# MCU.net
KiCad netlist of a schematic drawn in Altium Designer
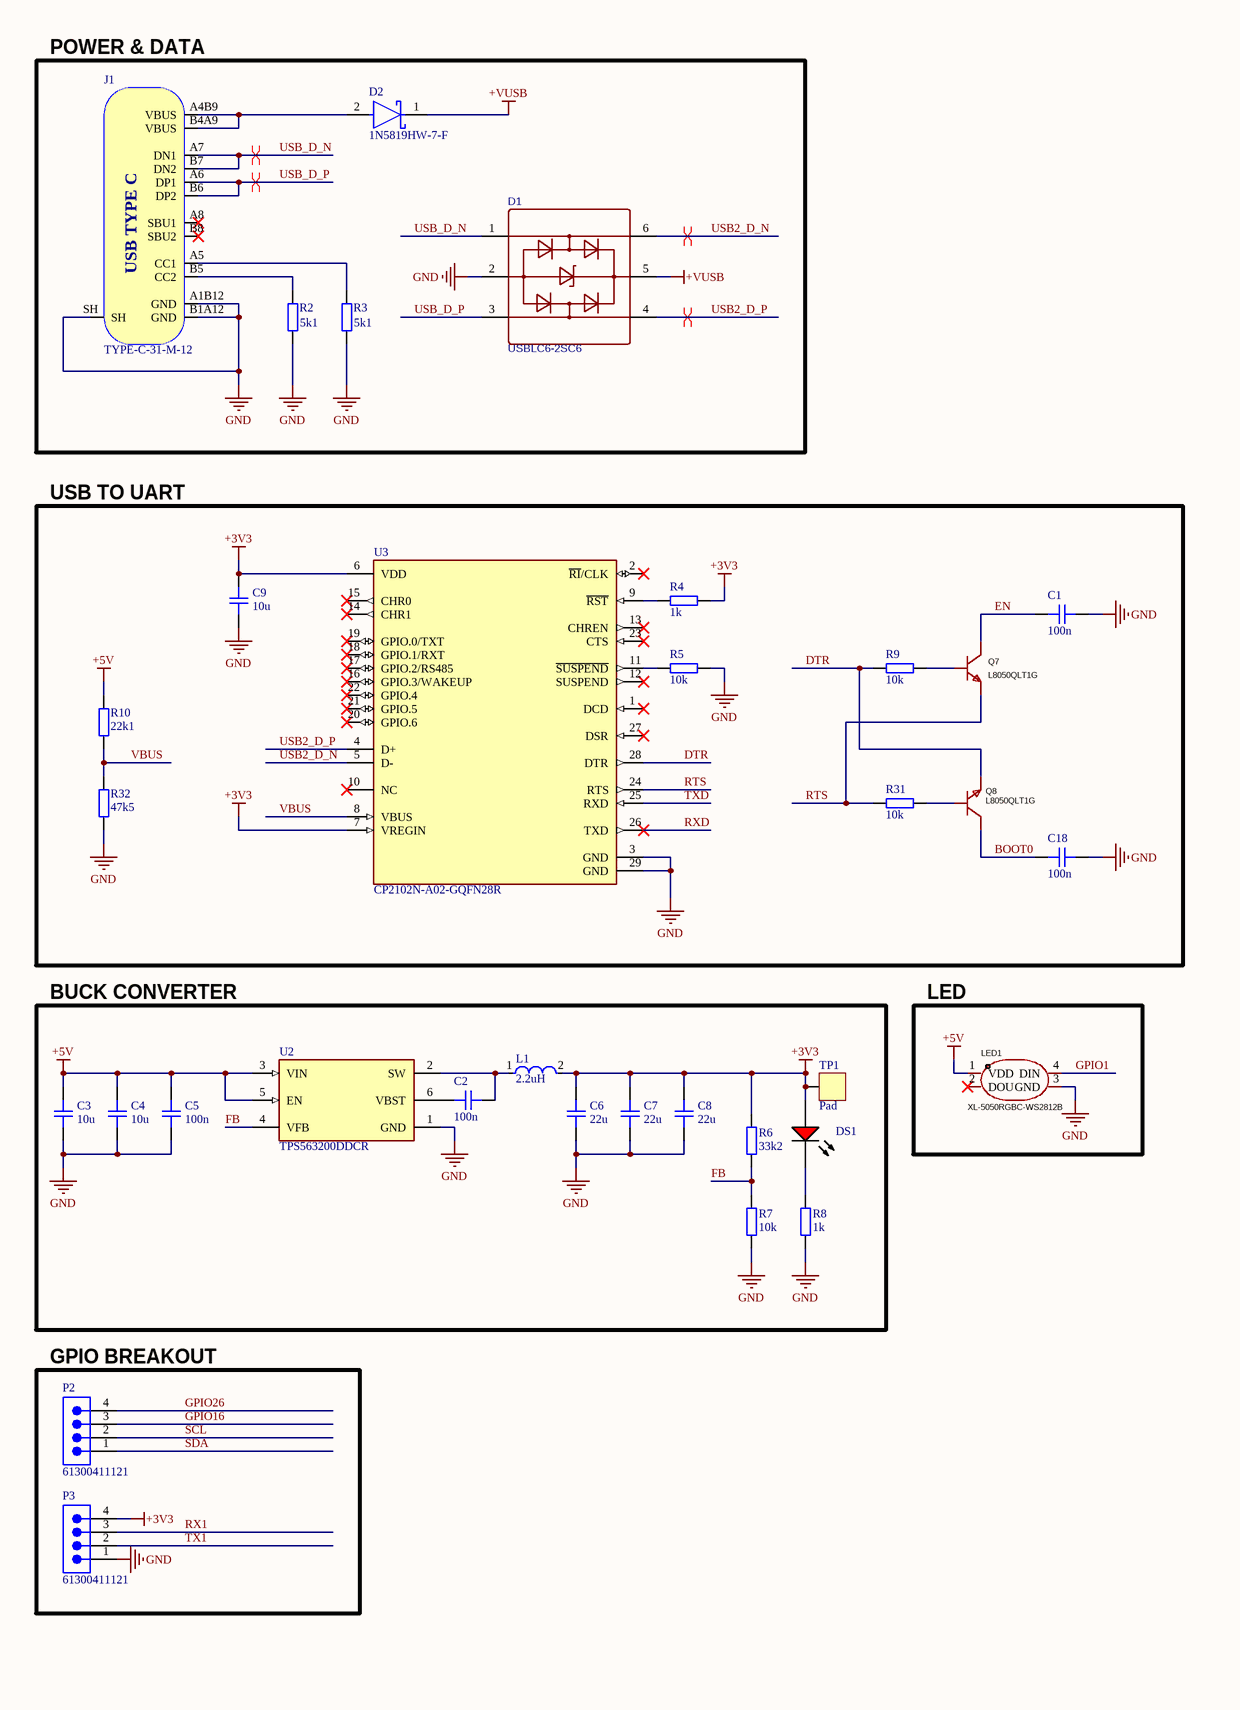
[diagram p0: MCU.SchDoc, left]
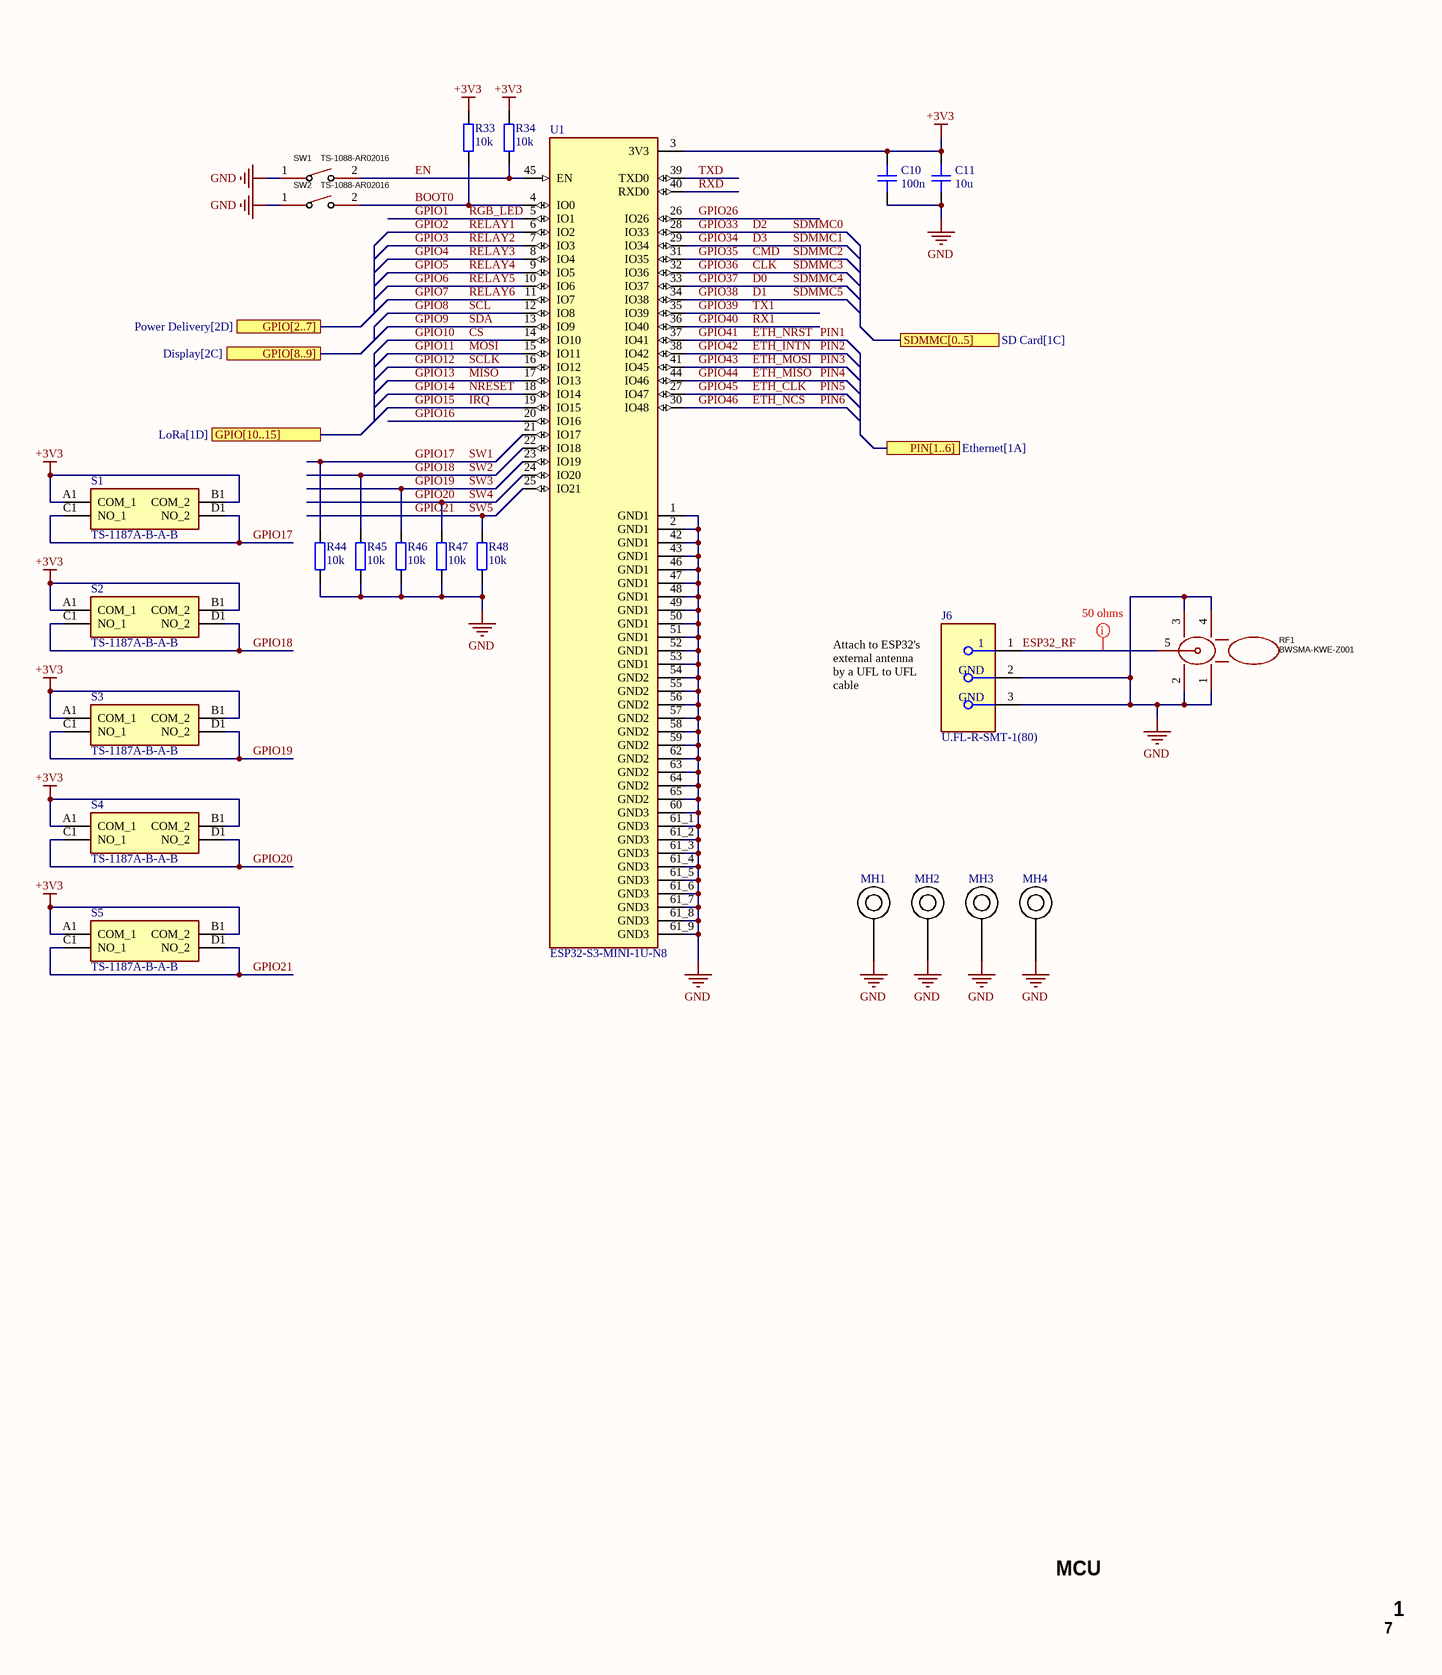
[diagram p1: MCU.SchDoc, right]

(export (version "E")
  (design (tool "Eeschema 10.0.6"))
  (components
    (comp (ref "C1")
      (value "CL05B104KB54PNC")
      (footprint "CAP_0402")
      (description "Capacitor SMD 0402")
      (fields (field (name "RATING") "100n"))
      (libsource (lib "Schematic-Lib-PhilsLab") (part "CAP_0402"))
    )
    (comp (ref "C2")
      (value "CL05B104KB54PNC")
      (footprint "CAP_0402")
      (description "Capacitor SMD 0402")
      (fields (field (name "RATING") "100n"))
      (libsource (lib "Schematic-Lib-PhilsLab") (part "CAP_0402"))
    )
    (comp (ref "C3")
      (value "10u")
      (footprint "CAP_0402")
      (description "Capacitor SMD 0402")
      (fields (field (name "Comment") "CL05A106MQ5NUNC"))
      (libsource (lib "Schematic-Lib-PhilsLab") (part "CAP_0402"))
    )
    (comp (ref "C4")
      (value "10u")
      (footprint "CAP_0402")
      (description "Capacitor SMD 0402")
      (fields (field (name "Comment") "CL05A106MQ5NUNC"))
      (libsource (lib "Schematic-Lib-PhilsLab") (part "CAP_0402"))
    )
    (comp (ref "C5")
      (value "CL05B104KB54PNC")
      (footprint "CAP_0402")
      (description "Capacitor SMD 0402")
      (fields (field (name "RATING") "100n"))
      (libsource (lib "Schematic-Lib-PhilsLab") (part "CAP_0402"))
    )
    (comp (ref "C6")
      (value "GRM158R61A226ME15D")
      (footprint "CAP_0402")
      (description "Capacitor SMD 0402")
      (fields (field (name "RATING") "22u"))
      (libsource (lib "Schematic-Lib-PhilsLab") (part "CAP_0402"))
    )
    (comp (ref "C7")
      (value "GRM158R61A226ME15D")
      (footprint "CAP_0402")
      (description "Capacitor SMD 0402")
      (fields (field (name "RATING") "22u"))
      (libsource (lib "Schematic-Lib-PhilsLab") (part "CAP_0402"))
    )
    (comp (ref "C8")
      (value "GRM158R61A226ME15D")
      (footprint "CAP_0402")
      (description "Capacitor SMD 0402")
      (fields (field (name "RATING") "22u"))
      (libsource (lib "Schematic-Lib-PhilsLab") (part "CAP_0402"))
    )
    (comp (ref "C9")
      (value "10u")
      (footprint "CAP_0402")
      (description "Capacitor SMD 0402")
      (fields (field (name "Comment") "CL05A106MQ5NUNC"))
      (libsource (lib "Schematic-Lib-PhilsLab") (part "CAP_0402"))
    )
    (comp (ref "C10")
      (value "CL05B104KB54PNC")
      (footprint "CAP_0402")
      (description "Capacitor SMD 0402")
      (fields (field (name "RATING") "100n"))
      (libsource (lib "Schematic-Lib-PhilsLab") (part "CAP_0402"))
    )
    (comp (ref "C11")
      (value "10u")
      (footprint "CAP_0402")
      (description "Capacitor SMD 0402")
      (fields (field (name "Comment") "CL05A106MQ5NUNC"))
      (libsource (lib "Schematic-Lib-PhilsLab") (part "CAP_0402"))
    )
    (comp (ref "C18")
      (value "CL05B104KB54PNC")
      (footprint "CAP_0402")
      (description "Capacitor SMD 0402")
      (fields (field (name "RATING") "100n"))
      (libsource (lib "Schematic-Lib-PhilsLab") (part "CAP_0402"))
    )
    (comp (ref "D1")
      (value "USBLC6-2SC6")
      (footprint "SOT-23-6_L2.9-W1.6-P0.95-LS2.8-BL")
      (fields (field (name "MANUFACTURER") "ST(意法半导体)"))
      (libsource (lib "JLCPCB_parts_library") (part "USBLC6-2SC6"))
    )
    (comp (ref "D2")
      (value "1N5819HW-7-F")
      (footprint "FP-SOD123-IPC_A")
      (description "DIODE SCHOTTKY 40V 1A SOD123")
      (libsource (lib "Altium Content Vault") (part "1d6ec82d83fb6aee721767c19dac4b9"))
    )
    (comp (ref "DS1")
      (value "LTST-C170KRKT")
      (footprint "LTST-C170KRKT_V")
      (description "LED Red, 75 mW, 54 mcd, -55 to 85 degC, 2-Pin SMD, RoHS, Tape and Reel")
      (fields (field (name "MANUFACTURER") "Lite-On"))
      (libsource (lib "Altium Content Vault") (part "LED-RED-AK-2"))
    )
    (comp (ref "J1")
      (value "TYPE-C-31-M-12")
      (footprint "TYPE-C-31-M-12")
      (description "USB Type C Connector Horizontal SMT")
      (fields (field (name "MANUFACTURER") "Koren Hroparts"))
      (libsource (lib "Schematic-Lib-PhilsLab") (part "TYPE-C-31-M-12"))
    )
    (comp (ref "J6")
      (value "U.FL-R-SMT-1(80)")
      (footprint "FP-U_FL-R-SMT-1_80-MFG")
      (description "CONN U.FL RCPT STR 50 OHM SMD")
      (libsource (lib "Altium Content Vault") (part "ad010367dc7cd7c7a13299a56582dd6"))
    )
    (comp (ref "L1")
      (value "IHLP1212BZER2R2M11")
      (footprint "FP-IHLP-1212BZ-11-MFG")
      (description "FIXED IND 2.2UH 3A 46 MOHM SMD")
      (fields (field (name "INDUCTANCE") "2.2uH") (field (name "TOLERANCE") "20%"))
      (libsource (lib "Altium Content Vault") (part "725321dda6339637d4d059423bc1c3c"))
    )
    (comp (ref "LED1")
      (value "XL-5050RGBC-WS2812B")
      (footprint "LED-SMD_4P-L5.0-W5.0-BL_XL-5050RGBC")
      (fields (field (name "MANUFACTURER") "XINGLIGHT(成兴光)"))
      (libsource (lib "JLCPCB_parts_library") (part "XL-5050RGBC-WS2812B_1"))
    )
    (comp (ref "MH1")
      (value "M3PlatedMountingHole2")
      (footprint "PCBComponent_1 - duplicate")
      (libsource (lib "JLCPCB_parts_library") (part "M3PlatedMountingHole2"))
    )
    (comp (ref "MH2")
      (value "M3PlatedMountingHole2")
      (footprint "PCBComponent_1 - duplicate")
      (libsource (lib "JLCPCB_parts_library") (part "M3PlatedMountingHole2"))
    )
    (comp (ref "MH3")
      (value "M3PlatedMountingHole2")
      (footprint "PCBComponent_1 - duplicate")
      (libsource (lib "JLCPCB_parts_library") (part "M3PlatedMountingHole2"))
    )
    (comp (ref "MH4")
      (value "M3PlatedMountingHole2")
      (footprint "PCBComponent_1 - duplicate")
      (libsource (lib "JLCPCB_parts_library") (part "M3PlatedMountingHole2"))
    )
    (comp (ref "P2")
      (value "61300411121")
      (footprint "61300411121")
      (libsource (lib "Altium Content Vault") (part "Header_Male_1R_04P"))
    )
    (comp (ref "P3")
      (value "61300411121")
      (footprint "61300411121")
      (libsource (lib "Altium Content Vault") (part "Header_Male_1R_04P"))
    )
    (comp (ref "Q7")
      (value "L8050QLT1G")
      (footprint "SOT-23-3_L2.9-W1.3-P1.90-LS2.4-BR")
      (fields (field (name "MANUFACTURER") "LRC(乐山无线电)"))
      (libsource (lib "JLCPCB_parts_library") (part "L8050QLT1G"))
    )
    (comp (ref "Q8")
      (value "L8050QLT1G")
      (footprint "SOT-23-3_L2.9-W1.3-P1.90-LS2.4-BR")
      (fields (field (name "MANUFACTURER") "LRC(乐山无线电)"))
      (libsource (lib "JLCPCB_parts_library") (part "L8050QLT1G"))
    )
    (comp (ref "R2")
      (value "5k1")
      (footprint "RES_0402")
      (description "Resistor SMD 0402 5.1k")
      (fields (field (name "Comment") "0402WGF5101TCE"))
      (libsource (lib "Schematic-Lib-PhilsLab") (part "RES_0402"))
    )
    (comp (ref "R3")
      (value "5k1")
      (footprint "RES_0402")
      (description "Resistor SMD 0402 5.1k")
      (fields (field (name "Comment") "0402WGF5101TCE"))
      (libsource (lib "Schematic-Lib-PhilsLab") (part "RES_0402"))
    )
    (comp (ref "R4")
      (value "1k")
      (footprint "RES_0402")
      (description "Resistor SMD 0402")
      (fields (field (name "Comment") "0402WGF1001TCE"))
      (libsource (lib "Schematic-Lib-PhilsLab") (part "RES_0402"))
    )
    (comp (ref "R5")
      (value "10k")
      (footprint "RES_0402")
      (description "Resistor SMD 0402")
      (fields (field (name "Comment") "0402WGF1002TCE"))
      (libsource (lib "Schematic-Lib-PhilsLab") (part "RES_0402"))
    )
    (comp (ref "R6")
      (value "33k2")
      (footprint "RES_0402")
      (description "Resistor SMD 0402")
      (fields (field (name "Comment") "0402WGF3322TCE"))
      (libsource (lib "Schematic-Lib-PhilsLab") (part "RES_0402"))
    )
    (comp (ref "R7")
      (value "10k")
      (footprint "RES_0402")
      (description "Resistor SMD 0402")
      (fields (field (name "Comment") "0402WGF1002TCE"))
      (libsource (lib "Schematic-Lib-PhilsLab") (part "RES_0402"))
    )
    (comp (ref "R8")
      (value "1k")
      (footprint "RES_0402")
      (description "Resistor SMD 0402")
      (fields (field (name "Comment") "0402WGF1001TCE"))
      (libsource (lib "Schematic-Lib-PhilsLab") (part "RES_0402"))
    )
    (comp (ref "R9")
      (value "10k")
      (footprint "RES_0402")
      (description "Resistor SMD 0402")
      (fields (field (name "Comment") "0402WGF1002TCE"))
      (libsource (lib "Schematic-Lib-PhilsLab") (part "RES_0402"))
    )
    (comp (ref "R10")
      (value "0402WGF2212TCE")
      (footprint "RES_0402")
      (description "Resistor SMD 0402")
      (fields (field (name "RATING") "22k1"))
      (libsource (lib "Schematic-Lib-PhilsLab") (part "RES_0402"))
    )
    (comp (ref "R31")
      (value "10k")
      (footprint "RES_0402")
      (description "Resistor SMD 0402")
      (fields (field (name "Comment") "0402WGF1002TCE"))
      (libsource (lib "Schematic-Lib-PhilsLab") (part "RES_0402"))
    )
    (comp (ref "R32")
      (value "RC0402FR-0747K5L")
      (footprint "RES_0402")
      (description "Resistor SMD 0402")
      (fields (field (name "PARAMETER 1") "47k5"))
      (libsource (lib "Schematic-Lib-PhilsLab") (part "RES_0402"))
    )
    (comp (ref "R33")
      (value "10k")
      (footprint "RES_0402")
      (description "Resistor SMD 0402")
      (fields (field (name "Comment") "0402WGF1002TCE"))
      (libsource (lib "Schematic-Lib-PhilsLab") (part "RES_0402"))
    )
    (comp (ref "R34")
      (value "10k")
      (footprint "RES_0402")
      (description "Resistor SMD 0402")
      (fields (field (name "Comment") "0402WGF1002TCE"))
      (libsource (lib "Schematic-Lib-PhilsLab") (part "RES_0402"))
    )
    (comp (ref "R44")
      (value "10k")
      (footprint "RES_0402")
      (description "Resistor SMD 0402")
      (fields (field (name "Comment") "0402WGF1002TCE"))
      (libsource (lib "Schematic-Lib-PhilsLab") (part "RES_0402"))
    )
    (comp (ref "R45")
      (value "10k")
      (footprint "RES_0402")
      (description "Resistor SMD 0402")
      (fields (field (name "Comment") "0402WGF1002TCE"))
      (libsource (lib "Schematic-Lib-PhilsLab") (part "RES_0402"))
    )
    (comp (ref "R46")
      (value "10k")
      (footprint "RES_0402")
      (description "Resistor SMD 0402")
      (fields (field (name "Comment") "0402WGF1002TCE"))
      (libsource (lib "Schematic-Lib-PhilsLab") (part "RES_0402"))
    )
    (comp (ref "R47")
      (value "10k")
      (footprint "RES_0402")
      (description "Resistor SMD 0402")
      (fields (field (name "Comment") "0402WGF1002TCE"))
      (libsource (lib "Schematic-Lib-PhilsLab") (part "RES_0402"))
    )
    (comp (ref "R48")
      (value "10k")
      (footprint "RES_0402")
      (description "Resistor SMD 0402")
      (fields (field (name "Comment") "0402WGF1002TCE"))
      (libsource (lib "Schematic-Lib-PhilsLab") (part "RES_0402"))
    )
    (comp (ref "RF1")
      (value "BWSMA-KWE-Z001")
      (footprint "SMA-TH_BWSMA-KWE-Z001")
      (fields (field (name "MANUFACTURER") "BAT WIRELESS(蝙蝠无线)"))
      (libsource (lib "JLCPCB_parts_library") (part "BWSMA-KWE-Z001"))
    )
    (comp (ref "S1")
      (value "TS-1187A-B-A-B")
      (footprint "JLCPCB_parts_library:TS1187ABAB")
      (description "Switch")
      (libsource (lib "JLCPCB_parts_library") (part "TS-1187A-B-A-B"))
    )
    (comp (ref "S2")
      (value "TS-1187A-B-A-B")
      (footprint "JLCPCB_parts_library:TS1187ABAB")
      (description "Switch")
      (libsource (lib "JLCPCB_parts_library") (part "TS-1187A-B-A-B"))
    )
    (comp (ref "S3")
      (value "TS-1187A-B-A-B")
      (footprint "JLCPCB_parts_library:TS1187ABAB")
      (description "Switch")
      (libsource (lib "JLCPCB_parts_library") (part "TS-1187A-B-A-B"))
    )
    (comp (ref "S4")
      (value "TS-1187A-B-A-B")
      (footprint "JLCPCB_parts_library:TS1187ABAB")
      (description "Switch")
      (libsource (lib "JLCPCB_parts_library") (part "TS-1187A-B-A-B"))
    )
    (comp (ref "S5")
      (value "TS-1187A-B-A-B")
      (footprint "JLCPCB_parts_library:TS1187ABAB")
      (description "Switch")
      (libsource (lib "JLCPCB_parts_library") (part "TS-1187A-B-A-B"))
    )
    (comp (ref "SW1")
      (value "TS-1088-AR02016")
      (footprint "SW-SMD_L3.9-W3.0-P4.45")
      (fields (field (name "MANUFACTURER") "XUNPU(讯普)"))
      (libsource (lib "JLCPCB_parts_library") (part "TS-1088-AR02016"))
    )
    (comp (ref "SW2")
      (value "TS-1088-AR02016")
      (footprint "SW-SMD_L3.9-W3.0-P4.45")
      (fields (field (name "MANUFACTURER") "XUNPU(讯普)"))
      (libsource (lib "JLCPCB_parts_library") (part "TS-1088-AR02016"))
    )
    (comp (ref "TP1")
      (value "Pad")
      (footprint "PAD_SQ_2MM")
      (description "Test Point Square 2mm")
      (libsource (lib "Schematic-Lib-PhilsLab") (part "PAD_SQ_2MM"))
    )
    (comp (ref "U1")
      (value "ESP32-S3-MINI-1U-N8")
      (footprint "XCVR_ESP32-S3-MINI-1U-N8")
      (fields (field (name "MF") "Espressif Systems"))
      (libsource (lib "ESP32-S3-MINI-1U-N8") (part "ESP32-S3-MINI-1U-N8"))
    )
    (comp (ref "U2")
      (value "TPS563200DDCR")
      (footprint "FP-DDC0006A-MFG")
      (description "IC REG BUCK ADJ 3A TSOT23-6")
      (libsource (lib "Altium Content Vault") (part "31d0a13bcb823f7fa58c78a9b473f81"))
    )
    (comp (ref "U3")
      (value "CP2102N-A02-GQFN28R")
      (footprint "FP-CP2102N-A02-GQFN28R-MFG")
      (description "IC USB TO UART BRIDGE QFN28")
      (libsource (lib "Altium Content Vault") (part "670edaef084fb69d2a747396d70a05e"))
    )
  )
  (nets
    (net (code "1") (name "+3V3") (class "Default")
      (node (ref "C10") (pin "2") (pinfunction "2_2") (pintype "passive"))
      (node (ref "C11") (pin "2") (pinfunction "2_2") (pintype "passive"))
      (node (ref "C6") (pin "2") (pinfunction "2_2") (pintype "passive"))
      (node (ref "C7") (pin "2") (pinfunction "2_2") (pintype "passive"))
      (node (ref "C8") (pin "2") (pinfunction "2_2") (pintype "passive"))
      (node (ref "C9") (pin "2") (pinfunction "2_2") (pintype "passive"))
      (node (ref "DS1") (pin "1") (pinfunction "A_1") (pintype "passive"))
      (node (ref "L1") (pin "2") (pinfunction "2_2") (pintype "passive"))
      (node (ref "P3") (pin "4") (pinfunction "4_4") (pintype "passive"))
      (node (ref "R33") (pin "1") (pinfunction "1_1") (pintype "passive"))
      (node (ref "R34") (pin "1") (pinfunction "1_1") (pintype "passive"))
      (node (ref "R4") (pin "1") (pinfunction "1_1") (pintype "passive"))
      (node (ref "R6") (pin "2") (pinfunction "2_2") (pintype "passive"))
      (node (ref "S1") (pin "A1") (pinfunction "COM_1_A1") (pintype "passive"))
      (node (ref "S1") (pin "B1") (pinfunction "COM_2_B1") (pintype "passive"))
      (node (ref "S2") (pin "A1") (pinfunction "COM_1_A1") (pintype "passive"))
      (node (ref "S2") (pin "B1") (pinfunction "COM_2_B1") (pintype "passive"))
      (node (ref "S3") (pin "A1") (pinfunction "COM_1_A1") (pintype "passive"))
      (node (ref "S3") (pin "B1") (pinfunction "COM_2_B1") (pintype "passive"))
      (node (ref "S4") (pin "A1") (pinfunction "COM_1_A1") (pintype "passive"))
      (node (ref "S4") (pin "B1") (pinfunction "COM_2_B1") (pintype "passive"))
      (node (ref "S5") (pin "A1") (pinfunction "COM_1_A1") (pintype "passive"))
      (node (ref "S5") (pin "B1") (pinfunction "COM_2_B1") (pintype "passive"))
      (node (ref "TP1") (pin "1") (pinfunction "1_1") (pintype "passive"))
      (node (ref "U1") (pin "3") (pinfunction "3V3_3") (pintype "power_in"))
      (node (ref "U3") (pin "6") (pinfunction "VDD_6") (pintype "power_in"))
      (node (ref "U3") (pin "7") (pinfunction "VREGIN_7") (pintype "input"))
    )
    (net (code "2") (name "+5V") (class "Default")
      (node (ref "C3") (pin "2") (pinfunction "2_2") (pintype "passive"))
      (node (ref "C4") (pin "2") (pinfunction "2_2") (pintype "passive"))
      (node (ref "C5") (pin "2") (pinfunction "2_2") (pintype "passive"))
      (node (ref "LED1") (pin "1") (pinfunction "VDD_1") (pintype "passive"))
      (node (ref "R10") (pin "2") (pinfunction "2_2") (pintype "passive"))
      (node (ref "U2") (pin "3") (pinfunction "VIN_3") (pintype "input"))
      (node (ref "U2") (pin "5") (pinfunction "EN_5") (pintype "input"))
    )
    (net (code "3") (name "+VUSB") (class "Default")
      (node (ref "D1") (pin "5") (pinfunction "5_5") (pintype "passive"))
      (node (ref "D2") (pin "1") (pinfunction "C_1") (pintype "passive"))
    )
    (net (code "4") (name "/BOOT0") (class "Default")
      (node (ref "C18") (pin "2") (pinfunction "2_2") (pintype "passive"))
      (node (ref "Q8") (pin "3") (pinfunction "C_3") (pintype "passive"))
      (node (ref "R33") (pin "2") (pinfunction "2_2") (pintype "passive"))
      (node (ref "SW2") (pin "2") (pinfunction "2_2") (pintype "passive"))
      (node (ref "U1") (pin "4") (pinfunction "IO0_4") (pintype "bidirectional"))
    )
    (net (code "5") (name "/DTR") (class "Default")
      (node (ref "Q8") (pin "2") (pinfunction "E_2") (pintype "passive"))
      (node (ref "R9") (pin "2") (pinfunction "2_2") (pintype "passive"))
      (node (ref "U3") (pin "28") (pinfunction "DTR_28") (pintype "output"))
    )
    (net (code "6") (name "/EN") (class "Default")
      (node (ref "C1") (pin "2") (pinfunction "2_2") (pintype "passive"))
      (node (ref "Q7") (pin "3") (pinfunction "C_3") (pintype "passive"))
      (node (ref "R34") (pin "2") (pinfunction "2_2") (pintype "passive"))
      (node (ref "SW1") (pin "2") (pinfunction "2_2") (pintype "passive"))
      (node (ref "U1") (pin "45") (pinfunction "EN_45") (pintype "input"))
    )
    (net (code "7") (name "/ESP32_RF") (class "Default")
      (node (ref "J6") (pin "1") (pinfunction "1_1") (pintype "passive"))
      (node (ref "RF1") (pin "5") (pinfunction "5_5") (pintype "passive"))
    )
    (net (code "8") (name "/FB") (class "Default")
      (node (ref "R6") (pin "1") (pinfunction "1_1") (pintype "passive"))
      (node (ref "R7") (pin "2") (pinfunction "2_2") (pintype "passive"))
      (node (ref "U2") (pin "4") (pinfunction "VFB_4") (pintype "passive"))
    )
    (net (code "9") (name "/GPIO1") (class "Default")
      (node (ref "LED1") (pin "4") (pinfunction "DIN_4") (pintype "passive"))
      (node (ref "U1") (pin "5") (pinfunction "IO1_5") (pintype "bidirectional"))
    )
    (net (code "10") (name "/GPIO2") (class "Default")
      (node (ref "U1") (pin "6") (pinfunction "IO2_6") (pintype "bidirectional"))
    )
    (net (code "11") (name "/GPIO3") (class "Default")
      (node (ref "U1") (pin "7") (pinfunction "IO3_7") (pintype "bidirectional"))
    )
    (net (code "12") (name "/GPIO4") (class "Default")
      (node (ref "U1") (pin "8") (pinfunction "IO4_8") (pintype "bidirectional"))
    )
    (net (code "13") (name "/GPIO5") (class "Default")
      (node (ref "U1") (pin "9") (pinfunction "IO5_9") (pintype "bidirectional"))
    )
    (net (code "14") (name "/GPIO6") (class "Default")
      (node (ref "U1") (pin "10") (pinfunction "IO6_10") (pintype "bidirectional"))
    )
    (net (code "15") (name "/GPIO7") (class "Default")
      (node (ref "U1") (pin "11") (pinfunction "IO7_11") (pintype "bidirectional"))
    )
    (net (code "16") (name "/GPIO8") (class "Default")
      (node (ref "P2") (pin "2") (pinfunction "2_2") (pintype "passive"))
      (node (ref "U1") (pin "12") (pinfunction "IO8_12") (pintype "bidirectional"))
    )
    (net (code "17") (name "/GPIO9") (class "Default")
      (node (ref "P2") (pin "1") (pinfunction "1_1") (pintype "passive"))
      (node (ref "U1") (pin "13") (pinfunction "IO9_13") (pintype "bidirectional"))
    )
    (net (code "18") (name "/GPIO10") (class "Default")
      (node (ref "U1") (pin "14") (pinfunction "IO10_14") (pintype "bidirectional"))
    )
    (net (code "19") (name "/GPIO11") (class "Default")
      (node (ref "U1") (pin "15") (pinfunction "IO11_15") (pintype "bidirectional"))
    )
    (net (code "20") (name "/GPIO12") (class "Default")
      (node (ref "U1") (pin "16") (pinfunction "IO12_16") (pintype "bidirectional"))
    )
    (net (code "21") (name "/GPIO13") (class "Default")
      (node (ref "U1") (pin "17") (pinfunction "IO13_17") (pintype "bidirectional"))
    )
    (net (code "22") (name "/GPIO14") (class "Default")
      (node (ref "U1") (pin "18") (pinfunction "IO14_18") (pintype "bidirectional"))
    )
    (net (code "23") (name "/GPIO15") (class "Default")
      (node (ref "U1") (pin "19") (pinfunction "IO15_19") (pintype "bidirectional"))
    )
    (net (code "24") (name "/GPIO16") (class "Default")
      (node (ref "P2") (pin "3") (pinfunction "3_3") (pintype "passive"))
      (node (ref "U1") (pin "20") (pinfunction "IO16_20") (pintype "bidirectional"))
    )
    (net (code "25") (name "/GPIO17") (class "Default")
      (node (ref "R44") (pin "1") (pinfunction "1_1") (pintype "passive"))
      (node (ref "S1") (pin "C1") (pinfunction "NO_1_C1") (pintype "passive"))
      (node (ref "S1") (pin "D1") (pinfunction "NO_2_D1") (pintype "passive"))
      (node (ref "U1") (pin "21") (pinfunction "IO17_21") (pintype "bidirectional"))
    )
    (net (code "26") (name "/GPIO18") (class "Default")
      (node (ref "R45") (pin "1") (pinfunction "1_1") (pintype "passive"))
      (node (ref "S2") (pin "C1") (pinfunction "NO_1_C1") (pintype "passive"))
      (node (ref "S2") (pin "D1") (pinfunction "NO_2_D1") (pintype "passive"))
      (node (ref "U1") (pin "22") (pinfunction "IO18_22") (pintype "bidirectional"))
    )
    (net (code "27") (name "/GPIO19") (class "Default")
      (node (ref "R46") (pin "1") (pinfunction "1_1") (pintype "passive"))
      (node (ref "S3") (pin "C1") (pinfunction "NO_1_C1") (pintype "passive"))
      (node (ref "S3") (pin "D1") (pinfunction "NO_2_D1") (pintype "passive"))
      (node (ref "U1") (pin "23") (pinfunction "IO19_23") (pintype "bidirectional"))
    )
    (net (code "28") (name "/GPIO20") (class "Default")
      (node (ref "R47") (pin "1") (pinfunction "1_1") (pintype "passive"))
      (node (ref "S4") (pin "C1") (pinfunction "NO_1_C1") (pintype "passive"))
      (node (ref "S4") (pin "D1") (pinfunction "NO_2_D1") (pintype "passive"))
      (node (ref "U1") (pin "24") (pinfunction "IO20_24") (pintype "bidirectional"))
    )
    (net (code "29") (name "/GPIO21") (class "Default")
      (node (ref "R48") (pin "1") (pinfunction "1_1") (pintype "passive"))
      (node (ref "S5") (pin "C1") (pinfunction "NO_1_C1") (pintype "passive"))
      (node (ref "S5") (pin "D1") (pinfunction "NO_2_D1") (pintype "passive"))
      (node (ref "U1") (pin "25") (pinfunction "IO21_25") (pintype "bidirectional"))
    )
    (net (code "30") (name "/GPIO26") (class "Default")
      (node (ref "P2") (pin "4") (pinfunction "4_4") (pintype "passive"))
      (node (ref "U1") (pin "26") (pinfunction "IO26_26") (pintype "bidirectional"))
    )
    (net (code "31") (name "/GPIO39") (class "Default")
      (node (ref "P3") (pin "2") (pinfunction "2_2") (pintype "passive"))
      (node (ref "U1") (pin "35") (pinfunction "IO39_35") (pintype "bidirectional"))
    )
    (net (code "32") (name "/GPIO40") (class "Default")
      (node (ref "P3") (pin "3") (pinfunction "3_3") (pintype "passive"))
      (node (ref "U1") (pin "36") (pinfunction "IO40_36") (pintype "bidirectional"))
    )
    (net (code "36") (name "/PIN1") (class "Default")
      (node (ref "U1") (pin "37") (pinfunction "IO41_37") (pintype "bidirectional"))
    )
    (net (code "37") (name "/PIN2") (class "Default")
      (node (ref "U1") (pin "38") (pinfunction "IO42_38") (pintype "bidirectional"))
    )
    (net (code "38") (name "/PIN3") (class "Default")
      (node (ref "U1") (pin "41") (pinfunction "IO45_41") (pintype "bidirectional"))
    )
    (net (code "39") (name "/PIN4") (class "Default")
      (node (ref "U1") (pin "44") (pinfunction "IO46_44") (pintype "bidirectional"))
    )
    (net (code "40") (name "/PIN5") (class "Default")
      (node (ref "U1") (pin "27") (pinfunction "IO47_27") (pintype "bidirectional"))
    )
    (net (code "41") (name "/PIN6") (class "Default")
      (node (ref "U1") (pin "30") (pinfunction "IO48_30") (pintype "bidirectional"))
    )
    (net (code "43") (name "/RTS") (class "Default")
      (node (ref "Q7") (pin "2") (pinfunction "E_2") (pintype "passive"))
      (node (ref "R31") (pin "2") (pinfunction "2_2") (pintype "passive"))
      (node (ref "U3") (pin "24") (pinfunction "RTS_24") (pintype "output"))
    )
    (net (code "44") (name "/RXD") (class "Default")
      (node (ref "U1") (pin "40") (pinfunction "RXD0_40") (pintype "bidirectional"))
      (node (ref "U3") (pin "26") (pinfunction "TXD_26") (pintype "output"))
    )
    (net (code "45") (name "/SDMMC0") (class "Default")
      (node (ref "U1") (pin "28") (pinfunction "IO33_28") (pintype "bidirectional"))
    )
    (net (code "46") (name "/SDMMC1") (class "Default")
      (node (ref "U1") (pin "29") (pinfunction "IO34_29") (pintype "bidirectional"))
    )
    (net (code "47") (name "/SDMMC2") (class "Default")
      (node (ref "U1") (pin "31") (pinfunction "IO35_31") (pintype "bidirectional"))
    )
    (net (code "48") (name "/SDMMC3") (class "Default")
      (node (ref "U1") (pin "32") (pinfunction "IO36_32") (pintype "bidirectional"))
    )
    (net (code "49") (name "/SDMMC4") (class "Default")
      (node (ref "U1") (pin "33") (pinfunction "IO37_33") (pintype "bidirectional"))
    )
    (net (code "50") (name "/SDMMC5") (class "Default")
      (node (ref "U1") (pin "34") (pinfunction "IO38_34") (pintype "bidirectional"))
    )
    (net (code "52") (name "/TXD") (class "Default")
      (node (ref "U1") (pin "39") (pinfunction "TXD0_39") (pintype "bidirectional"))
      (node (ref "U3") (pin "25") (pinfunction "RXD_25") (pintype "input"))
    )
    (net (code "53") (name "/USB2_D_N") (class "Default")
      (node (ref "D1") (pin "6") (pinfunction "6_6") (pintype "passive"))
      (node (ref "U3") (pin "5") (pinfunction "D-_5") (pintype "passive"))
    )
    (net (code "54") (name "/USB2_D_P") (class "Default")
      (node (ref "D1") (pin "4") (pinfunction "4_4") (pintype "passive"))
      (node (ref "U3") (pin "4") (pinfunction "D+_4") (pintype "passive"))
    )
    (net (code "55") (name "/USB_D_N") (class "Default")
      (node (ref "D1") (pin "1") (pinfunction "1_1") (pintype "passive"))
      (node (ref "J1") (pin "A7") (pinfunction "DN1_A7") (pintype "bidirectional"))
      (node (ref "J1") (pin "B7") (pinfunction "DN2_B7") (pintype "bidirectional"))
    )
    (net (code "56") (name "/USB_D_P") (class "Default")
      (node (ref "D1") (pin "3") (pinfunction "3_3") (pintype "passive"))
      (node (ref "J1") (pin "A6") (pinfunction "DP1_A6") (pintype "bidirectional"))
      (node (ref "J1") (pin "B6") (pinfunction "DP2_B6") (pintype "bidirectional"))
    )
    (net (code "57") (name "/VBUS") (class "Default")
      (node (ref "R10") (pin "1") (pinfunction "1_1") (pintype "passive"))
      (node (ref "R32") (pin "2") (pinfunction "2_2") (pintype "passive"))
      (node (ref "U3") (pin "8") (pinfunction "VBUS_8") (pintype "input"))
    )
    (net (code "58") (name "GND") (class "Default")
      (node (ref "C1") (pin "1") (pinfunction "1_1") (pintype "passive"))
      (node (ref "C10") (pin "1") (pinfunction "1_1") (pintype "passive"))
      (node (ref "C11") (pin "1") (pinfunction "1_1") (pintype "passive"))
      (node (ref "C18") (pin "1") (pinfunction "1_1") (pintype "passive"))
      (node (ref "C3") (pin "1") (pinfunction "1_1") (pintype "passive"))
      (node (ref "C4") (pin "1") (pinfunction "1_1") (pintype "passive"))
      (node (ref "C5") (pin "1") (pinfunction "1_1") (pintype "passive"))
      (node (ref "C6") (pin "1") (pinfunction "1_1") (pintype "passive"))
      (node (ref "C7") (pin "1") (pinfunction "1_1") (pintype "passive"))
      (node (ref "C8") (pin "1") (pinfunction "1_1") (pintype "passive"))
      (node (ref "C9") (pin "1") (pinfunction "1_1") (pintype "passive"))
      (node (ref "D1") (pin "2") (pinfunction "2_2") (pintype "passive"))
      (node (ref "J1") (pin "A1B12") (pinfunction "GND_A1B12") (pintype "power_in"))
      (node (ref "J1") (pin "B1A12") (pinfunction "GND_B1A12") (pintype "power_in"))
      (node (ref "J1") (pin "SH") (pinfunction "SH_SH") (pintype "power_in"))
      (node (ref "J6") (pin "2") (pinfunction "GND_2") (pintype "power_in"))
      (node (ref "J6") (pin "3") (pinfunction "GND_3") (pintype "power_in"))
      (node (ref "LED1") (pin "3") (pinfunction "GND_3") (pintype "passive"))
      (node (ref "MH1") (pin "1") (pinfunction "1_1") (pintype "passive"))
      (node (ref "MH2") (pin "1") (pinfunction "1_1") (pintype "passive"))
      (node (ref "MH3") (pin "1") (pinfunction "1_1") (pintype "passive"))
      (node (ref "MH4") (pin "1") (pinfunction "1_1") (pintype "passive"))
      (node (ref "P3") (pin "1") (pinfunction "1_1") (pintype "passive"))
      (node (ref "R2") (pin "2") (pinfunction "2_2") (pintype "passive"))
      (node (ref "R3") (pin "2") (pinfunction "2_2") (pintype "passive"))
      (node (ref "R32") (pin "1") (pinfunction "1_1") (pintype "passive"))
      (node (ref "R44") (pin "2") (pinfunction "2_2") (pintype "passive"))
      (node (ref "R45") (pin "2") (pinfunction "2_2") (pintype "passive"))
      (node (ref "R46") (pin "2") (pinfunction "2_2") (pintype "passive"))
      (node (ref "R47") (pin "2") (pinfunction "2_2") (pintype "passive"))
      (node (ref "R48") (pin "2") (pinfunction "2_2") (pintype "passive"))
      (node (ref "R5") (pin "1") (pinfunction "1_1") (pintype "passive"))
      (node (ref "R7") (pin "1") (pinfunction "1_1") (pintype "passive"))
      (node (ref "R8") (pin "1") (pinfunction "1_1") (pintype "passive"))
      (node (ref "RF1") (pin "1") (pinfunction "1_1") (pintype "passive"))
      (node (ref "RF1") (pin "2") (pinfunction "2_2") (pintype "passive"))
      (node (ref "RF1") (pin "3") (pinfunction "3_3") (pintype "passive"))
      (node (ref "RF1") (pin "4") (pinfunction "4_4") (pintype "passive"))
      (node (ref "SW1") (pin "1") (pinfunction "1_1") (pintype "passive"))
      (node (ref "SW2") (pin "1") (pinfunction "1_1") (pintype "passive"))
      (node (ref "U1") (pin "1") (pinfunction "GND1_1") (pintype "power_in"))
      (node (ref "U1") (pin "2") (pinfunction "GND1_2") (pintype "power_in"))
      (node (ref "U1") (pin "42") (pinfunction "GND1_42") (pintype "power_in"))
      (node (ref "U1") (pin "43") (pinfunction "GND1_43") (pintype "power_in"))
      (node (ref "U1") (pin "46") (pinfunction "GND1_46") (pintype "power_in"))
      (node (ref "U1") (pin "47") (pinfunction "GND1_47") (pintype "power_in"))
      (node (ref "U1") (pin "48") (pinfunction "GND1_48") (pintype "power_in"))
      (node (ref "U1") (pin "49") (pinfunction "GND1_49") (pintype "power_in"))
      (node (ref "U1") (pin "50") (pinfunction "GND1_50") (pintype "power_in"))
      (node (ref "U1") (pin "51") (pinfunction "GND1_51") (pintype "power_in"))
      (node (ref "U1") (pin "52") (pinfunction "GND1_52") (pintype "power_in"))
      (node (ref "U1") (pin "53") (pinfunction "GND1_53") (pintype "power_in"))
      (node (ref "U1") (pin "54") (pinfunction "GND2_54") (pintype "power_in"))
      (node (ref "U1") (pin "55") (pinfunction "GND2_55") (pintype "power_in"))
      (node (ref "U1") (pin "56") (pinfunction "GND2_56") (pintype "power_in"))
      (node (ref "U1") (pin "57") (pinfunction "GND2_57") (pintype "power_in"))
      (node (ref "U1") (pin "58") (pinfunction "GND2_58") (pintype "power_in"))
      (node (ref "U1") (pin "59") (pinfunction "GND2_59") (pintype "power_in"))
      (node (ref "U1") (pin "60") (pinfunction "GND3_60") (pintype "power_in"))
      (node (ref "U1") (pin "61_1") (pinfunction "GND3_61_1") (pintype "power_in"))
      (node (ref "U1") (pin "61_2") (pinfunction "GND3_61_2") (pintype "power_in"))
      (node (ref "U1") (pin "61_3") (pinfunction "GND3_61_3") (pintype "power_in"))
      (node (ref "U1") (pin "61_4") (pinfunction "GND3_61_4") (pintype "power_in"))
      (node (ref "U1") (pin "61_5") (pinfunction "GND3_61_5") (pintype "power_in"))
      (node (ref "U1") (pin "61_6") (pinfunction "GND3_61_6") (pintype "power_in"))
      (node (ref "U1") (pin "61_7") (pinfunction "GND3_61_7") (pintype "power_in"))
      (node (ref "U1") (pin "61_8") (pinfunction "GND3_61_8") (pintype "power_in"))
      (node (ref "U1") (pin "61_9") (pinfunction "GND3_61_9") (pintype "power_in"))
      (node (ref "U1") (pin "62") (pinfunction "GND2_62") (pintype "power_in"))
      (node (ref "U1") (pin "63") (pinfunction "GND2_63") (pintype "power_in"))
      (node (ref "U1") (pin "64") (pinfunction "GND2_64") (pintype "power_in"))
      (node (ref "U1") (pin "65") (pinfunction "GND2_65") (pintype "power_in"))
      (node (ref "U2") (pin "1") (pinfunction "GND_1") (pintype "power_in"))
      (node (ref "U3") (pin "29") (pinfunction "GND_29") (pintype "power_in"))
      (node (ref "U3") (pin "3") (pinfunction "GND_3") (pintype "power_in"))
    )
    (net (code "59") (name "Net-(D2-A)") (class "Default")
      (node (ref "D2") (pin "2") (pinfunction "A_2") (pintype "passive"))
      (node (ref "J1") (pin "A4B9") (pinfunction "VBUS_A4B9") (pintype "power_in"))
      (node (ref "J1") (pin "B4A9") (pinfunction "VBUS_B4A9") (pintype "power_in"))
    )
    (net (code "60") (name "Net-(DS1-K)") (class "Default")
      (node (ref "DS1") (pin "2") (pinfunction "K_2") (pintype "passive"))
      (node (ref "R8") (pin "2") (pinfunction "2_2") (pintype "passive"))
    )
    (net (code "61") (name "Net-(J1-CC1)") (class "Default")
      (node (ref "J1") (pin "A5") (pinfunction "CC1_A5") (pintype "passive"))
      (node (ref "R3") (pin "1") (pinfunction "1_1") (pintype "passive"))
    )
    (net (code "62") (name "Net-(J1-CC2)") (class "Default")
      (node (ref "J1") (pin "B5") (pinfunction "CC2_B5") (pintype "tri_state"))
      (node (ref "R2") (pin "1") (pinfunction "1_1") (pintype "passive"))
    )
    (net (code "63") (name "Net-(Q7-B)") (class "Default")
      (node (ref "Q7") (pin "1") (pinfunction "B_1") (pintype "passive"))
      (node (ref "R9") (pin "1") (pinfunction "1_1") (pintype "passive"))
    )
    (net (code "64") (name "Net-(Q8-B)") (class "Default")
      (node (ref "Q8") (pin "1") (pinfunction "B_1") (pintype "passive"))
      (node (ref "R31") (pin "1") (pinfunction "1_1") (pintype "passive"))
    )
    (net (code "65") (name "Net-(U2-SW)") (class "Default")
      (node (ref "C2") (pin "1") (pinfunction "1_1") (pintype "passive"))
      (node (ref "L1") (pin "1") (pinfunction "1_1") (pintype "passive"))
      (node (ref "U2") (pin "2") (pinfunction "SW_2") (pintype "passive"))
    )
    (net (code "66") (name "Net-(U2-VBST)") (class "Default")
      (node (ref "C2") (pin "2") (pinfunction "2_2") (pintype "passive"))
      (node (ref "U2") (pin "6") (pinfunction "VBST_6") (pintype "passive"))
    )
    (net (code "67") (name "Net-(U3-~{RST})") (class "Default")
      (node (ref "R4") (pin "2") (pinfunction "2_2") (pintype "passive"))
      (node (ref "U3") (pin "9") (pinfunction "~{RST}_9") (pintype "input"))
    )
    (net (code "68") (name "Net-(U3-~{SUSPEND})") (class "Default")
      (node (ref "R5") (pin "2") (pinfunction "2_2") (pintype "passive"))
      (node (ref "U3") (pin "11") (pinfunction "~{SUSPEND}_11") (pintype "output"))
    )
    (net (code "69") (name "unconnected-(J1-SBU1-PadA8)") (class "Default")
      (node (ref "J1") (pin "A8") (pinfunction "SBU1_A8") (pintype "bidirectional+no_connect"))
    )
    (net (code "70") (name "unconnected-(J1-SBU2-PadB8)") (class "Default")
      (node (ref "J1") (pin "B8") (pinfunction "SBU2_B8") (pintype "bidirectional+no_connect"))
    )
    (net (code "71") (name "unconnected-(LED1-DOU-Pad2)") (class "Default")
      (node (ref "LED1") (pin "2") (pinfunction "DOU_2") (pintype "passive+no_connect"))
    )
    (net (code "72") (name "unconnected-(U3-CHR0-Pad15)") (class "Default")
      (node (ref "U3") (pin "15") (pinfunction "CHR0_15") (pintype "output+no_connect"))
    )
    (net (code "73") (name "unconnected-(U3-CHR1-Pad14)") (class "Default")
      (node (ref "U3") (pin "14") (pinfunction "CHR1_14") (pintype "output+no_connect"))
    )
    (net (code "74") (name "unconnected-(U3-CHREN-Pad13)") (class "Default")
      (node (ref "U3") (pin "13") (pinfunction "CHREN_13") (pintype "output+no_connect"))
    )
    (net (code "75") (name "unconnected-(U3-CTS-Pad23)") (class "Default")
      (node (ref "U3") (pin "23") (pinfunction "CTS_23") (pintype "input+no_connect"))
    )
    (net (code "76") (name "unconnected-(U3-DCD-Pad1)") (class "Default")
      (node (ref "U3") (pin "1") (pinfunction "DCD_1") (pintype "input+no_connect"))
    )
    (net (code "77") (name "unconnected-(U3-DSR-Pad27)") (class "Default")
      (node (ref "U3") (pin "27") (pinfunction "DSR_27") (pintype "input+no_connect"))
    )
    (net (code "78") (name "unconnected-(U3-GPIO.0{slash}TXT-Pad19)") (class "Default")
      (node (ref "U3") (pin "19") (pinfunction "GPIO.0/TXT_19") (pintype "bidirectional+no_connect"))
    )
    (net (code "79") (name "unconnected-(U3-GPIO.1{slash}RXT-Pad18)") (class "Default")
      (node (ref "U3") (pin "18") (pinfunction "GPIO.1/RXT_18") (pintype "bidirectional+no_connect"))
    )
    (net (code "80") (name "unconnected-(U3-GPIO.2{slash}RS485-Pad17)") (class "Default")
      (node (ref "U3") (pin "17") (pinfunction "GPIO.2/RS485_17") (pintype "bidirectional+no_connect"))
    )
    (net (code "81") (name "unconnected-(U3-GPIO.3{slash}WAKEUP-Pad16)") (class "Default")
      (node (ref "U3") (pin "16") (pinfunction "GPIO.3/WAKEUP_16") (pintype "bidirectional+no_connect"))
    )
    (net (code "82") (name "unconnected-(U3-GPIO.4-Pad22)") (class "Default")
      (node (ref "U3") (pin "22") (pinfunction "GPIO.4_22") (pintype "bidirectional+no_connect"))
    )
    (net (code "83") (name "unconnected-(U3-GPIO.5-Pad21)") (class "Default")
      (node (ref "U3") (pin "21") (pinfunction "GPIO.5_21") (pintype "bidirectional+no_connect"))
    )
    (net (code "84") (name "unconnected-(U3-GPIO.6-Pad20)") (class "Default")
      (node (ref "U3") (pin "20") (pinfunction "GPIO.6_20") (pintype "bidirectional+no_connect"))
    )
    (net (code "85") (name "unconnected-(U3-NC-Pad10)") (class "Default")
      (node (ref "U3") (pin "10") (pinfunction "NC_10") (pintype "passive+no_connect"))
    )
    (net (code "86") (name "unconnected-(U3-SUSPEND-Pad12)") (class "Default")
      (node (ref "U3") (pin "12") (pinfunction "SUSPEND_12") (pintype "output+no_connect"))
    )
    (net (code "87") (name "unconnected-(U3-~{RI}{slash}CLK-Pad2)") (class "Default")
      (node (ref "U3") (pin "2") (pinfunction "~{RI}/CLK_2") (pintype "bidirectional+no_connect"))
    )
  )
)
